# Digital_Input.net
KiCad netlist of a schematic drawn in Altium Designer
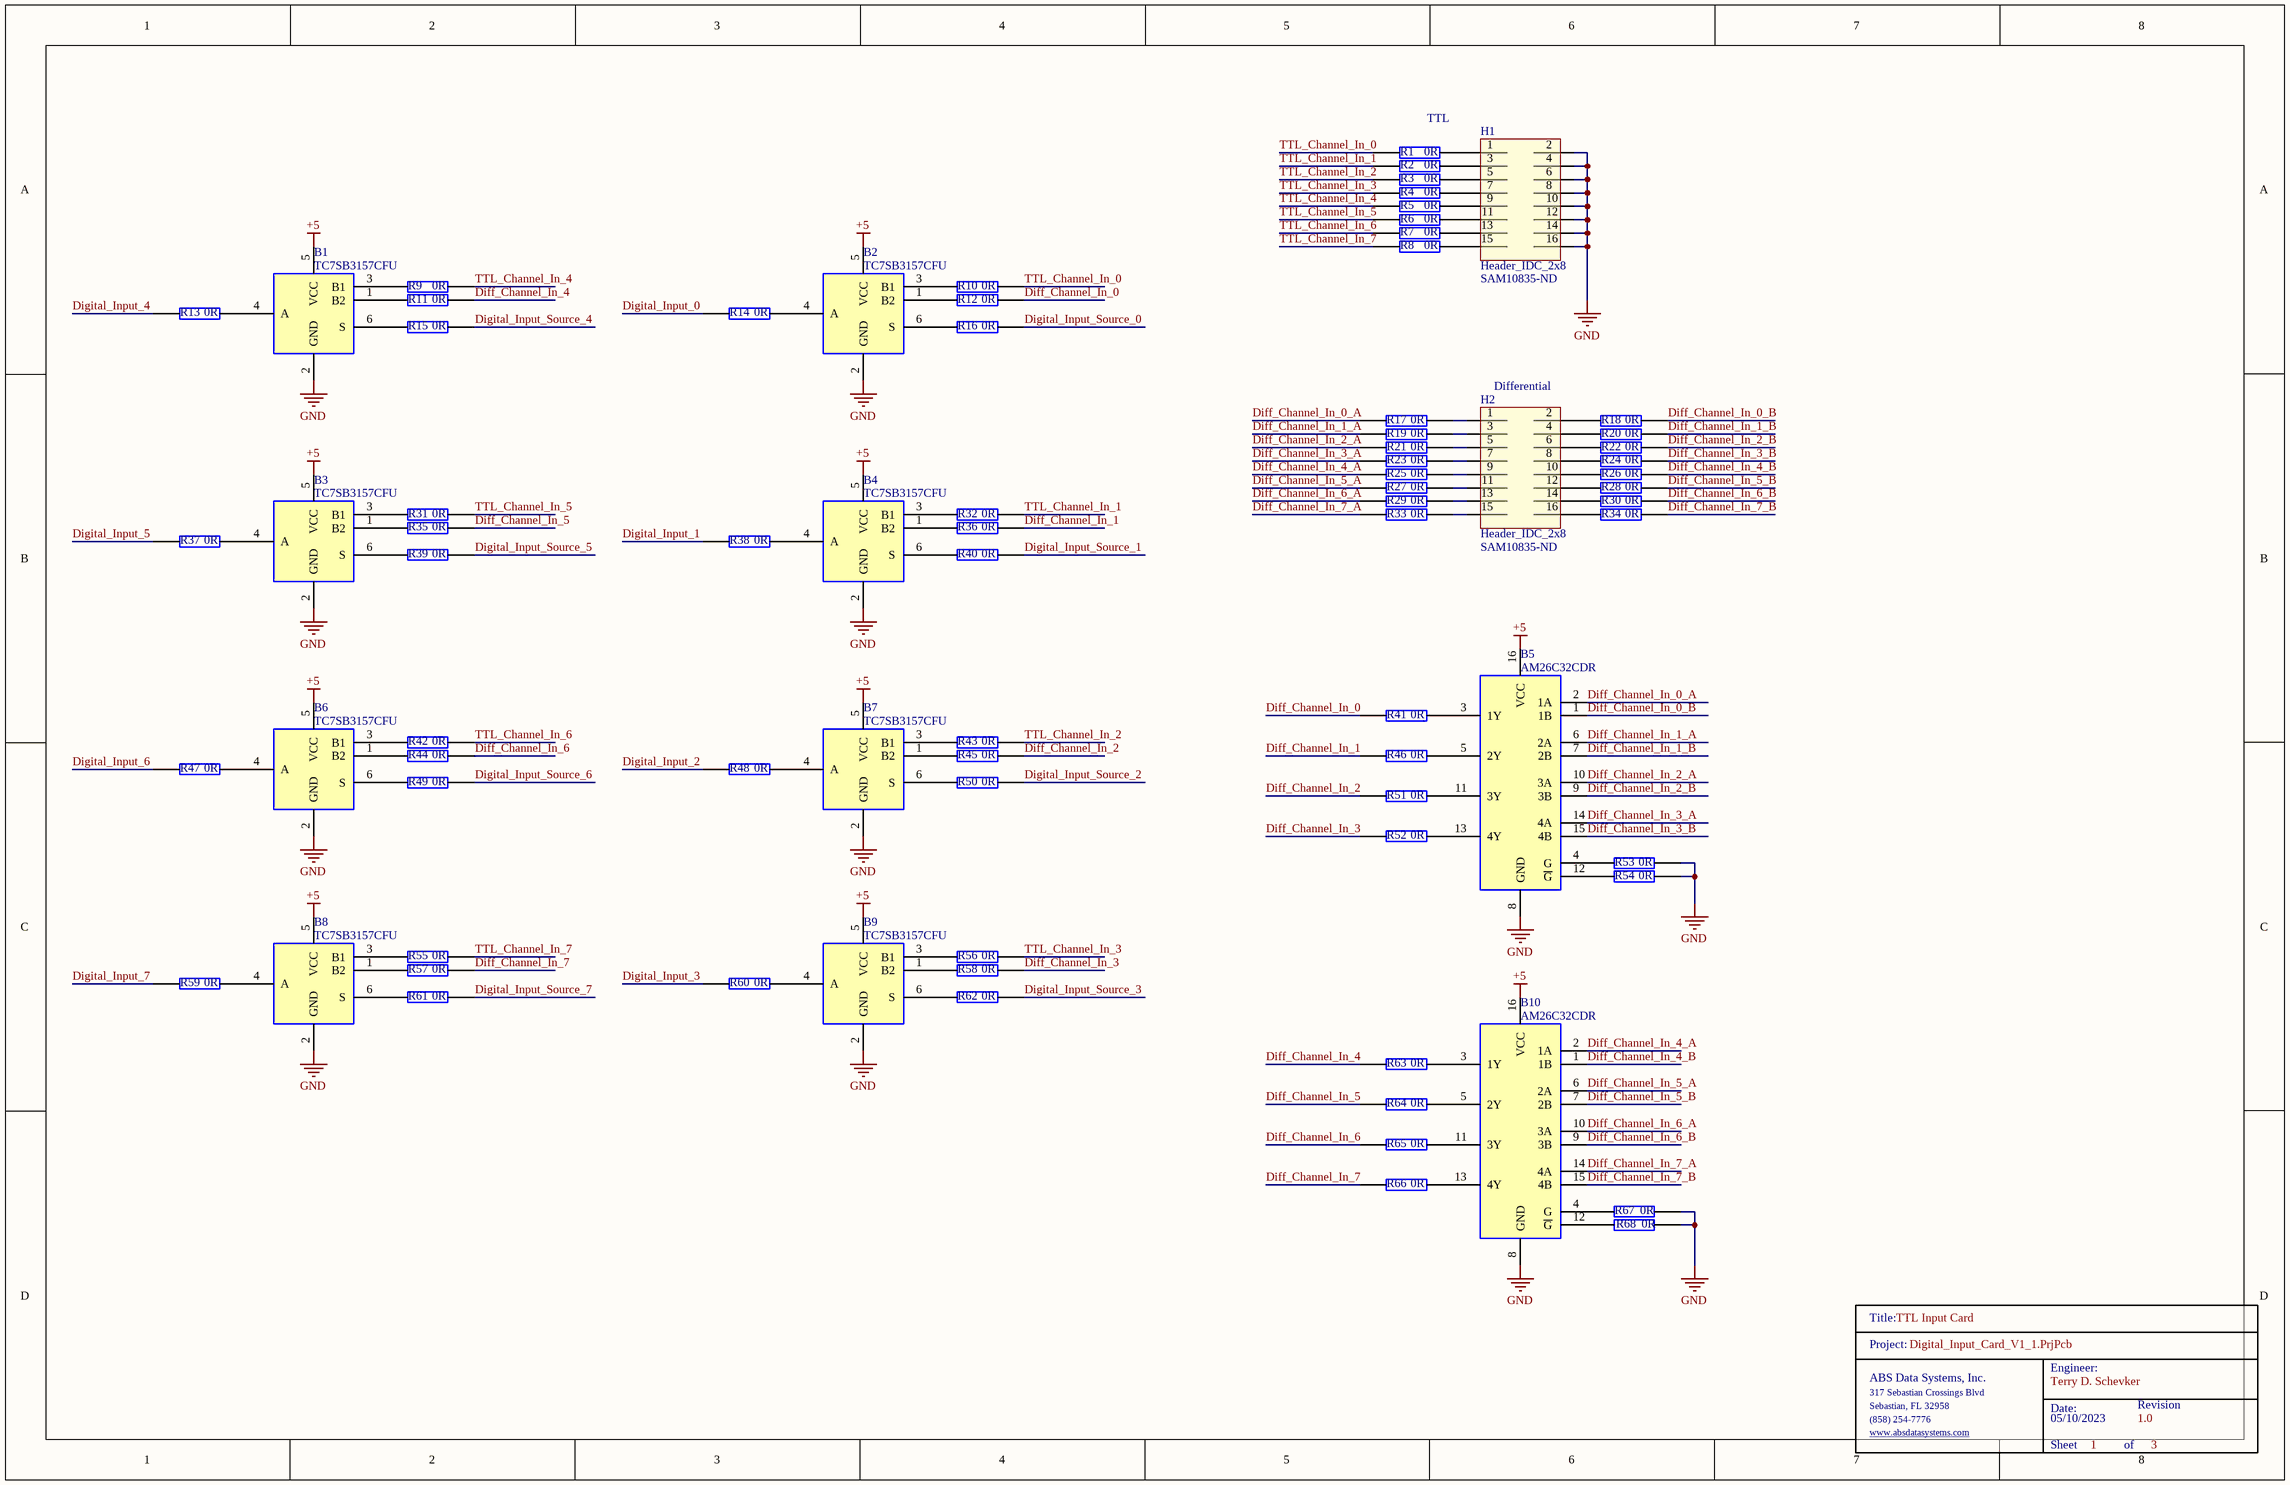
[diagram p0: Digital_Input.SchDoc]

(export (version "E")
  (design (tool "Eeschema 10.0.6"))
  (components
    (comp (ref "B1")
      (value "TC7SB3157CFU")
      (footprint "SOT-363-6")
      (description "TC7SB3157CFU MUX 2 in 1 out with control bit")
      (fields
        (field (name "MOUSER PART NUMBER") "771-PMP3906AYSH")
        (field (name "MANUFACTURER_PART_NUMBER") "PMP3906AYSH")
      )
      (libsource (lib "SemiConductors") (part "TC7SB3157CFU"))
    )
    (comp (ref "B2")
      (value "TC7SB3157CFU")
      (footprint "SOT-363-6")
      (description "TC7SB3157CFU MUX 2 in 1 out with control bit")
      (fields
        (field (name "MOUSER PART NUMBER") "771-PMP3906AYSH")
        (field (name "MANUFACTURER_PART_NUMBER") "PMP3906AYSH")
      )
      (libsource (lib "SemiConductors") (part "TC7SB3157CFU"))
    )
    (comp (ref "B3")
      (value "TC7SB3157CFU")
      (footprint "SOT-363-6")
      (description "TC7SB3157CFU MUX 2 in 1 out with control bit")
      (fields
        (field (name "MOUSER PART NUMBER") "771-PMP3906AYSH")
        (field (name "MANUFACTURER_PART_NUMBER") "PMP3906AYSH")
      )
      (libsource (lib "SemiConductors") (part "TC7SB3157CFU"))
    )
    (comp (ref "B4")
      (value "TC7SB3157CFU")
      (footprint "SOT-363-6")
      (description "TC7SB3157CFU MUX 2 in 1 out with control bit")
      (fields
        (field (name "MOUSER PART NUMBER") "771-PMP3906AYSH")
        (field (name "MANUFACTURER_PART_NUMBER") "PMP3906AYSH")
      )
      (libsource (lib "SemiConductors") (part "TC7SB3157CFU"))
    )
    (comp (ref "B5")
      (value "AM26C32CDR")
      (footprint "SOIC127P600X175-16N")
      (description "TEXAS INSTRUMENTS - AM26C32CDR - Receiver RS422/423, 4 Drivers, 4.5V-5.5V supply, SOIC-16")
      (fields (field (name "MOUSER PART NUMBER") "595-AM26C32CDR"))
      (libsource (lib "SemiConductors") (part "AM26C32CDR"))
    )
    (comp (ref "B6")
      (value "TC7SB3157CFU")
      (footprint "SOT-363-6")
      (description "TC7SB3157CFU MUX 2 in 1 out with control bit")
      (fields
        (field (name "MOUSER PART NUMBER") "771-PMP3906AYSH")
        (field (name "MANUFACTURER_PART_NUMBER") "PMP3906AYSH")
      )
      (libsource (lib "SemiConductors") (part "TC7SB3157CFU"))
    )
    (comp (ref "B7")
      (value "TC7SB3157CFU")
      (footprint "SOT-363-6")
      (description "TC7SB3157CFU MUX 2 in 1 out with control bit")
      (fields
        (field (name "MOUSER PART NUMBER") "771-PMP3906AYSH")
        (field (name "MANUFACTURER_PART_NUMBER") "PMP3906AYSH")
      )
      (libsource (lib "SemiConductors") (part "TC7SB3157CFU"))
    )
    (comp (ref "B8")
      (value "TC7SB3157CFU")
      (footprint "SOT-363-6")
      (description "TC7SB3157CFU MUX 2 in 1 out with control bit")
      (fields
        (field (name "MOUSER PART NUMBER") "771-PMP3906AYSH")
        (field (name "MANUFACTURER_PART_NUMBER") "PMP3906AYSH")
      )
      (libsource (lib "SemiConductors") (part "TC7SB3157CFU"))
    )
    (comp (ref "B9")
      (value "TC7SB3157CFU")
      (footprint "SOT-363-6")
      (description "TC7SB3157CFU MUX 2 in 1 out with control bit")
      (fields
        (field (name "MOUSER PART NUMBER") "771-PMP3906AYSH")
        (field (name "MANUFACTURER_PART_NUMBER") "PMP3906AYSH")
      )
      (libsource (lib "SemiConductors") (part "TC7SB3157CFU"))
    )
    (comp (ref "B10")
      (value "AM26C32CDR")
      (footprint "SOIC127P600X175-16N")
      (description "TEXAS INSTRUMENTS - AM26C32CDR - Receiver RS422/423, 4 Drivers, 4.5V-5.5V supply, SOIC-16")
      (fields (field (name "MOUSER PART NUMBER") "595-AM26C32CDR"))
      (libsource (lib "SemiConductors") (part "AM26C32CDR"))
    )
    (comp (ref "H1")
      (value "Header_IDC_2x8")
      (footprint "HDR2X8")
      (description "16 Pin 2x8 Through Hold IDC Connector")
      (fields
        (field (name "MANUFACTURER") "Samtec")
        (field (name "MANUFACTURER PART NUMBER") "TST-108-01-G-D")
        (field (name "SUPPLIER PART NUMBER 1") "SAM10835-ND")
      )
      (libsource (lib "Misc") (part "Header_IDC_2x8"))
    )
    (comp (ref "H2")
      (value "Header_IDC_2x8")
      (footprint "HDR2X8")
      (description "16 Pin 2x8 Through Hold IDC Connector")
      (fields
        (field (name "MANUFACTURER") "Samtec")
        (field (name "MANUFACTURER PART NUMBER") "TST-108-01-G-D")
        (field (name "SUPPLIER PART NUMBER 1") "SAM10835-ND")
      )
      (libsource (lib "Misc") (part "Header_IDC_2x8"))
    )
    (comp (ref "R1")
      (value "0R")
      (footprint "0603")
      (description "YAGEO 0603 0 ohm")
      (fields
        (field (name "MOUSER PART NUMBER") "603-RC0603JR-070RL")
        (field (name "MANUFACTURER_PART_NUMBER") "RC0603JR-070RL")
      )
      (libsource (lib "Resistors") (part "RC0603JR-070RL"))
    )
    (comp (ref "R2")
      (value "0R")
      (footprint "0603")
      (description "YAGEO 0603 0 ohm")
      (fields
        (field (name "MOUSER PART NUMBER") "603-RC0603JR-070RL")
        (field (name "MANUFACTURER_PART_NUMBER") "RC0603JR-070RL")
      )
      (libsource (lib "Resistors") (part "RC0603JR-070RL"))
    )
    (comp (ref "R3")
      (value "0R")
      (footprint "0603")
      (description "YAGEO 0603 0 ohm")
      (fields
        (field (name "MOUSER PART NUMBER") "603-RC0603JR-070RL")
        (field (name "MANUFACTURER_PART_NUMBER") "RC0603JR-070RL")
      )
      (libsource (lib "Resistors") (part "RC0603JR-070RL"))
    )
    (comp (ref "R4")
      (value "0R")
      (footprint "0603")
      (description "YAGEO 0603 0 ohm")
      (fields
        (field (name "MOUSER PART NUMBER") "603-RC0603JR-070RL")
        (field (name "MANUFACTURER_PART_NUMBER") "RC0603JR-070RL")
      )
      (libsource (lib "Resistors") (part "RC0603JR-070RL"))
    )
    (comp (ref "R5")
      (value "0R")
      (footprint "0603")
      (description "YAGEO 0603 0 ohm")
      (fields
        (field (name "MOUSER PART NUMBER") "603-RC0603JR-070RL")
        (field (name "MANUFACTURER_PART_NUMBER") "RC0603JR-070RL")
      )
      (libsource (lib "Resistors") (part "RC0603JR-070RL"))
    )
    (comp (ref "R6")
      (value "0R")
      (footprint "0603")
      (description "YAGEO 0603 0 ohm")
      (fields
        (field (name "MOUSER PART NUMBER") "603-RC0603JR-070RL")
        (field (name "MANUFACTURER_PART_NUMBER") "RC0603JR-070RL")
      )
      (libsource (lib "Resistors") (part "RC0603JR-070RL"))
    )
    (comp (ref "R7")
      (value "0R")
      (footprint "0603")
      (description "YAGEO 0603 0 ohm")
      (fields
        (field (name "MOUSER PART NUMBER") "603-RC0603JR-070RL")
        (field (name "MANUFACTURER_PART_NUMBER") "RC0603JR-070RL")
      )
      (libsource (lib "Resistors") (part "RC0603JR-070RL"))
    )
    (comp (ref "R8")
      (value "0R")
      (footprint "0603")
      (description "YAGEO 0603 0 ohm")
      (fields
        (field (name "MOUSER PART NUMBER") "603-RC0603JR-070RL")
        (field (name "MANUFACTURER_PART_NUMBER") "RC0603JR-070RL")
      )
      (libsource (lib "Resistors") (part "RC0603JR-070RL"))
    )
    (comp (ref "R9")
      (value "0R")
      (footprint "0603")
      (description "YAGEO 0603 0 ohm")
      (fields
        (field (name "MOUSER PART NUMBER") "603-RC0603JR-070RL")
        (field (name "MANUFACTURER_PART_NUMBER") "RC0603JR-070RL")
      )
      (libsource (lib "Resistors") (part "RC0603JR-070RL"))
    )
    (comp (ref "R10")
      (value "0R")
      (footprint "0603")
      (description "YAGEO 0603 0 ohm")
      (fields
        (field (name "MOUSER PART NUMBER") "603-RC0603JR-070RL")
        (field (name "MANUFACTURER_PART_NUMBER") "RC0603JR-070RL")
      )
      (libsource (lib "Resistors") (part "RC0603JR-070RL"))
    )
    (comp (ref "R11")
      (value "0R")
      (footprint "0603")
      (description "YAGEO 0603 0 ohm")
      (fields
        (field (name "MOUSER PART NUMBER") "603-RC0603JR-070RL")
        (field (name "MANUFACTURER_PART_NUMBER") "RC0603JR-070RL")
      )
      (libsource (lib "Resistors") (part "RC0603JR-070RL"))
    )
    (comp (ref "R12")
      (value "0R")
      (footprint "0603")
      (description "YAGEO 0603 0 ohm")
      (fields
        (field (name "MOUSER PART NUMBER") "603-RC0603JR-070RL")
        (field (name "MANUFACTURER_PART_NUMBER") "RC0603JR-070RL")
      )
      (libsource (lib "Resistors") (part "RC0603JR-070RL"))
    )
    (comp (ref "R13")
      (value "0R")
      (footprint "0603")
      (description "YAGEO 0603 0 ohm")
      (fields
        (field (name "MOUSER PART NUMBER") "603-RC0603JR-070RL")
        (field (name "MANUFACTURER_PART_NUMBER") "RC0603JR-070RL")
      )
      (libsource (lib "Resistors") (part "RC0603JR-070RL"))
    )
    (comp (ref "R14")
      (value "0R")
      (footprint "0603")
      (description "YAGEO 0603 0 ohm")
      (fields
        (field (name "MOUSER PART NUMBER") "603-RC0603JR-070RL")
        (field (name "MANUFACTURER_PART_NUMBER") "RC0603JR-070RL")
      )
      (libsource (lib "Resistors") (part "RC0603JR-070RL"))
    )
    (comp (ref "R15")
      (value "0R")
      (footprint "0603")
      (description "YAGEO 0603 0 ohm")
      (fields
        (field (name "MOUSER PART NUMBER") "603-RC0603JR-070RL")
        (field (name "MANUFACTURER_PART_NUMBER") "RC0603JR-070RL")
      )
      (libsource (lib "Resistors") (part "RC0603JR-070RL"))
    )
    (comp (ref "R16")
      (value "0R")
      (footprint "0603")
      (description "YAGEO 0603 0 ohm")
      (fields
        (field (name "MOUSER PART NUMBER") "603-RC0603JR-070RL")
        (field (name "MANUFACTURER_PART_NUMBER") "RC0603JR-070RL")
      )
      (libsource (lib "Resistors") (part "RC0603JR-070RL"))
    )
    (comp (ref "R17")
      (value "0R")
      (footprint "0603")
      (description "YAGEO 0603 0 ohm")
      (fields
        (field (name "MOUSER PART NUMBER") "603-RC0603JR-070RL")
        (field (name "MANUFACTURER_PART_NUMBER") "RC0603JR-070RL")
      )
      (libsource (lib "Resistors") (part "RC0603JR-070RL"))
    )
    (comp (ref "R18")
      (value "0R")
      (footprint "0603")
      (description "YAGEO 0603 0 ohm")
      (fields
        (field (name "MOUSER PART NUMBER") "603-RC0603JR-070RL")
        (field (name "MANUFACTURER_PART_NUMBER") "RC0603JR-070RL")
      )
      (libsource (lib "Resistors") (part "RC0603JR-070RL"))
    )
    (comp (ref "R19")
      (value "0R")
      (footprint "0603")
      (description "YAGEO 0603 0 ohm")
      (fields
        (field (name "MOUSER PART NUMBER") "603-RC0603JR-070RL")
        (field (name "MANUFACTURER_PART_NUMBER") "RC0603JR-070RL")
      )
      (libsource (lib "Resistors") (part "RC0603JR-070RL"))
    )
    (comp (ref "R20")
      (value "0R")
      (footprint "0603")
      (description "YAGEO 0603 0 ohm")
      (fields
        (field (name "MOUSER PART NUMBER") "603-RC0603JR-070RL")
        (field (name "MANUFACTURER_PART_NUMBER") "RC0603JR-070RL")
      )
      (libsource (lib "Resistors") (part "RC0603JR-070RL"))
    )
    (comp (ref "R21")
      (value "0R")
      (footprint "0603")
      (description "YAGEO 0603 0 ohm")
      (fields
        (field (name "MOUSER PART NUMBER") "603-RC0603JR-070RL")
        (field (name "MANUFACTURER_PART_NUMBER") "RC0603JR-070RL")
      )
      (libsource (lib "Resistors") (part "RC0603JR-070RL"))
    )
    (comp (ref "R22")
      (value "0R")
      (footprint "0603")
      (description "YAGEO 0603 0 ohm")
      (fields
        (field (name "MOUSER PART NUMBER") "603-RC0603JR-070RL")
        (field (name "MANUFACTURER_PART_NUMBER") "RC0603JR-070RL")
      )
      (libsource (lib "Resistors") (part "RC0603JR-070RL"))
    )
    (comp (ref "R23")
      (value "0R")
      (footprint "0603")
      (description "YAGEO 0603 0 ohm")
      (fields
        (field (name "MOUSER PART NUMBER") "603-RC0603JR-070RL")
        (field (name "MANUFACTURER_PART_NUMBER") "RC0603JR-070RL")
      )
      (libsource (lib "Resistors") (part "RC0603JR-070RL"))
    )
    (comp (ref "R24")
      (value "0R")
      (footprint "0603")
      (description "YAGEO 0603 0 ohm")
      (fields
        (field (name "MOUSER PART NUMBER") "603-RC0603JR-070RL")
        (field (name "MANUFACTURER_PART_NUMBER") "RC0603JR-070RL")
      )
      (libsource (lib "Resistors") (part "RC0603JR-070RL"))
    )
    (comp (ref "R25")
      (value "0R")
      (footprint "0603")
      (description "YAGEO 0603 0 ohm")
      (fields
        (field (name "MOUSER PART NUMBER") "603-RC0603JR-070RL")
        (field (name "MANUFACTURER_PART_NUMBER") "RC0603JR-070RL")
      )
      (libsource (lib "Resistors") (part "RC0603JR-070RL"))
    )
    (comp (ref "R26")
      (value "0R")
      (footprint "0603")
      (description "YAGEO 0603 0 ohm")
      (fields
        (field (name "MOUSER PART NUMBER") "603-RC0603JR-070RL")
        (field (name "MANUFACTURER_PART_NUMBER") "RC0603JR-070RL")
      )
      (libsource (lib "Resistors") (part "RC0603JR-070RL"))
    )
    (comp (ref "R27")
      (value "0R")
      (footprint "0603")
      (description "YAGEO 0603 0 ohm")
      (fields
        (field (name "MOUSER PART NUMBER") "603-RC0603JR-070RL")
        (field (name "MANUFACTURER_PART_NUMBER") "RC0603JR-070RL")
      )
      (libsource (lib "Resistors") (part "RC0603JR-070RL"))
    )
    (comp (ref "R28")
      (value "0R")
      (footprint "0603")
      (description "YAGEO 0603 0 ohm")
      (fields
        (field (name "MOUSER PART NUMBER") "603-RC0603JR-070RL")
        (field (name "MANUFACTURER_PART_NUMBER") "RC0603JR-070RL")
      )
      (libsource (lib "Resistors") (part "RC0603JR-070RL"))
    )
    (comp (ref "R29")
      (value "0R")
      (footprint "0603")
      (description "YAGEO 0603 0 ohm")
      (fields
        (field (name "MOUSER PART NUMBER") "603-RC0603JR-070RL")
        (field (name "MANUFACTURER_PART_NUMBER") "RC0603JR-070RL")
      )
      (libsource (lib "Resistors") (part "RC0603JR-070RL"))
    )
    (comp (ref "R30")
      (value "0R")
      (footprint "0603")
      (description "YAGEO 0603 0 ohm")
      (fields
        (field (name "MOUSER PART NUMBER") "603-RC0603JR-070RL")
        (field (name "MANUFACTURER_PART_NUMBER") "RC0603JR-070RL")
      )
      (libsource (lib "Resistors") (part "RC0603JR-070RL"))
    )
    (comp (ref "R31")
      (value "0R")
      (footprint "0603")
      (description "YAGEO 0603 0 ohm")
      (fields
        (field (name "MOUSER PART NUMBER") "603-RC0603JR-070RL")
        (field (name "MANUFACTURER_PART_NUMBER") "RC0603JR-070RL")
      )
      (libsource (lib "Resistors") (part "RC0603JR-070RL"))
    )
    (comp (ref "R32")
      (value "0R")
      (footprint "0603")
      (description "YAGEO 0603 0 ohm")
      (fields
        (field (name "MOUSER PART NUMBER") "603-RC0603JR-070RL")
        (field (name "MANUFACTURER_PART_NUMBER") "RC0603JR-070RL")
      )
      (libsource (lib "Resistors") (part "RC0603JR-070RL"))
    )
    (comp (ref "R33")
      (value "0R")
      (footprint "0603")
      (description "YAGEO 0603 0 ohm")
      (fields
        (field (name "MOUSER PART NUMBER") "603-RC0603JR-070RL")
        (field (name "MANUFACTURER_PART_NUMBER") "RC0603JR-070RL")
      )
      (libsource (lib "Resistors") (part "RC0603JR-070RL"))
    )
    (comp (ref "R34")
      (value "0R")
      (footprint "0603")
      (description "YAGEO 0603 0 ohm")
      (fields
        (field (name "MOUSER PART NUMBER") "603-RC0603JR-070RL")
        (field (name "MANUFACTURER_PART_NUMBER") "RC0603JR-070RL")
      )
      (libsource (lib "Resistors") (part "RC0603JR-070RL"))
    )
    (comp (ref "R35")
      (value "0R")
      (footprint "0603")
      (description "YAGEO 0603 0 ohm")
      (fields
        (field (name "MOUSER PART NUMBER") "603-RC0603JR-070RL")
        (field (name "MANUFACTURER_PART_NUMBER") "RC0603JR-070RL")
      )
      (libsource (lib "Resistors") (part "RC0603JR-070RL"))
    )
    (comp (ref "R36")
      (value "0R")
      (footprint "0603")
      (description "YAGEO 0603 0 ohm")
      (fields
        (field (name "MOUSER PART NUMBER") "603-RC0603JR-070RL")
        (field (name "MANUFACTURER_PART_NUMBER") "RC0603JR-070RL")
      )
      (libsource (lib "Resistors") (part "RC0603JR-070RL"))
    )
    (comp (ref "R37")
      (value "0R")
      (footprint "0603")
      (description "YAGEO 0603 0 ohm")
      (fields
        (field (name "MOUSER PART NUMBER") "603-RC0603JR-070RL")
        (field (name "MANUFACTURER_PART_NUMBER") "RC0603JR-070RL")
      )
      (libsource (lib "Resistors") (part "RC0603JR-070RL"))
    )
    (comp (ref "R38")
      (value "0R")
      (footprint "0603")
      (description "YAGEO 0603 0 ohm")
      (fields
        (field (name "MOUSER PART NUMBER") "603-RC0603JR-070RL")
        (field (name "MANUFACTURER_PART_NUMBER") "RC0603JR-070RL")
      )
      (libsource (lib "Resistors") (part "RC0603JR-070RL"))
    )
    (comp (ref "R39")
      (value "0R")
      (footprint "0603")
      (description "YAGEO 0603 0 ohm")
      (fields
        (field (name "MOUSER PART NUMBER") "603-RC0603JR-070RL")
        (field (name "MANUFACTURER_PART_NUMBER") "RC0603JR-070RL")
      )
      (libsource (lib "Resistors") (part "RC0603JR-070RL"))
    )
    (comp (ref "R40")
      (value "0R")
      (footprint "0603")
      (description "YAGEO 0603 0 ohm")
      (fields
        (field (name "MOUSER PART NUMBER") "603-RC0603JR-070RL")
        (field (name "MANUFACTURER_PART_NUMBER") "RC0603JR-070RL")
      )
      (libsource (lib "Resistors") (part "RC0603JR-070RL"))
    )
    (comp (ref "R41")
      (value "0R")
      (footprint "0603")
      (description "YAGEO 0603 0 ohm")
      (fields
        (field (name "MOUSER PART NUMBER") "603-RC0603JR-070RL")
        (field (name "MANUFACTURER_PART_NUMBER") "RC0603JR-070RL")
      )
      (libsource (lib "Resistors") (part "RC0603JR-070RL"))
    )
    (comp (ref "R42")
      (value "0R")
      (footprint "0603")
      (description "YAGEO 0603 0 ohm")
      (fields
        (field (name "MOUSER PART NUMBER") "603-RC0603JR-070RL")
        (field (name "MANUFACTURER_PART_NUMBER") "RC0603JR-070RL")
      )
      (libsource (lib "Resistors") (part "RC0603JR-070RL"))
    )
    (comp (ref "R43")
      (value "0R")
      (footprint "0603")
      (description "YAGEO 0603 0 ohm")
      (fields
        (field (name "MOUSER PART NUMBER") "603-RC0603JR-070RL")
        (field (name "MANUFACTURER_PART_NUMBER") "RC0603JR-070RL")
      )
      (libsource (lib "Resistors") (part "RC0603JR-070RL"))
    )
    (comp (ref "R44")
      (value "0R")
      (footprint "0603")
      (description "YAGEO 0603 0 ohm")
      (fields
        (field (name "MOUSER PART NUMBER") "603-RC0603JR-070RL")
        (field (name "MANUFACTURER_PART_NUMBER") "RC0603JR-070RL")
      )
      (libsource (lib "Resistors") (part "RC0603JR-070RL"))
    )
    (comp (ref "R45")
      (value "0R")
      (footprint "0603")
      (description "YAGEO 0603 0 ohm")
      (fields
        (field (name "MOUSER PART NUMBER") "603-RC0603JR-070RL")
        (field (name "MANUFACTURER_PART_NUMBER") "RC0603JR-070RL")
      )
      (libsource (lib "Resistors") (part "RC0603JR-070RL"))
    )
    (comp (ref "R46")
      (value "0R")
      (footprint "0603")
      (description "YAGEO 0603 0 ohm")
      (fields
        (field (name "MOUSER PART NUMBER") "603-RC0603JR-070RL")
        (field (name "MANUFACTURER_PART_NUMBER") "RC0603JR-070RL")
      )
      (libsource (lib "Resistors") (part "RC0603JR-070RL"))
    )
    (comp (ref "R47")
      (value "0R")
      (footprint "0603")
      (description "YAGEO 0603 0 ohm")
      (fields
        (field (name "MOUSER PART NUMBER") "603-RC0603JR-070RL")
        (field (name "MANUFACTURER_PART_NUMBER") "RC0603JR-070RL")
      )
      (libsource (lib "Resistors") (part "RC0603JR-070RL"))
    )
    (comp (ref "R48")
      (value "0R")
      (footprint "0603")
      (description "YAGEO 0603 0 ohm")
      (fields
        (field (name "MOUSER PART NUMBER") "603-RC0603JR-070RL")
        (field (name "MANUFACTURER_PART_NUMBER") "RC0603JR-070RL")
      )
      (libsource (lib "Resistors") (part "RC0603JR-070RL"))
    )
    (comp (ref "R49")
      (value "0R")
      (footprint "0603")
      (description "YAGEO 0603 0 ohm")
      (fields
        (field (name "MOUSER PART NUMBER") "603-RC0603JR-070RL")
        (field (name "MANUFACTURER_PART_NUMBER") "RC0603JR-070RL")
      )
      (libsource (lib "Resistors") (part "RC0603JR-070RL"))
    )
    (comp (ref "R50")
      (value "0R")
      (footprint "0603")
      (description "YAGEO 0603 0 ohm")
      (fields
        (field (name "MOUSER PART NUMBER") "603-RC0603JR-070RL")
        (field (name "MANUFACTURER_PART_NUMBER") "RC0603JR-070RL")
      )
      (libsource (lib "Resistors") (part "RC0603JR-070RL"))
    )
    (comp (ref "R51")
      (value "0R")
      (footprint "0603")
      (description "YAGEO 0603 0 ohm")
      (fields
        (field (name "MOUSER PART NUMBER") "603-RC0603JR-070RL")
        (field (name "MANUFACTURER_PART_NUMBER") "RC0603JR-070RL")
      )
      (libsource (lib "Resistors") (part "RC0603JR-070RL"))
    )
    (comp (ref "R52")
      (value "0R")
      (footprint "0603")
      (description "YAGEO 0603 0 ohm")
      (fields
        (field (name "MOUSER PART NUMBER") "603-RC0603JR-070RL")
        (field (name "MANUFACTURER_PART_NUMBER") "RC0603JR-070RL")
      )
      (libsource (lib "Resistors") (part "RC0603JR-070RL"))
    )
    (comp (ref "R53")
      (value "0R")
      (footprint "0603")
      (description "YAGEO 0603 0 ohm")
      (fields
        (field (name "MOUSER PART NUMBER") "603-RC0603JR-070RL")
        (field (name "MANUFACTURER_PART_NUMBER") "RC0603JR-070RL")
      )
      (libsource (lib "Resistors") (part "RC0603JR-070RL"))
    )
    (comp (ref "R54")
      (value "0R")
      (footprint "0603")
      (description "YAGEO 0603 0 ohm")
      (fields
        (field (name "MOUSER PART NUMBER") "603-RC0603JR-070RL")
        (field (name "MANUFACTURER_PART_NUMBER") "RC0603JR-070RL")
      )
      (libsource (lib "Resistors") (part "RC0603JR-070RL"))
    )
    (comp (ref "R55")
      (value "0R")
      (footprint "0603")
      (description "YAGEO 0603 0 ohm")
      (fields
        (field (name "MOUSER PART NUMBER") "603-RC0603JR-070RL")
        (field (name "MANUFACTURER_PART_NUMBER") "RC0603JR-070RL")
      )
      (libsource (lib "Resistors") (part "RC0603JR-070RL"))
    )
    (comp (ref "R56")
      (value "0R")
      (footprint "0603")
      (description "YAGEO 0603 0 ohm")
      (fields
        (field (name "MOUSER PART NUMBER") "603-RC0603JR-070RL")
        (field (name "MANUFACTURER_PART_NUMBER") "RC0603JR-070RL")
      )
      (libsource (lib "Resistors") (part "RC0603JR-070RL"))
    )
    (comp (ref "R57")
      (value "0R")
      (footprint "0603")
      (description "YAGEO 0603 0 ohm")
      (fields
        (field (name "MOUSER PART NUMBER") "603-RC0603JR-070RL")
        (field (name "MANUFACTURER_PART_NUMBER") "RC0603JR-070RL")
      )
      (libsource (lib "Resistors") (part "RC0603JR-070RL"))
    )
    (comp (ref "R58")
      (value "0R")
      (footprint "0603")
      (description "YAGEO 0603 0 ohm")
      (fields
        (field (name "MOUSER PART NUMBER") "603-RC0603JR-070RL")
        (field (name "MANUFACTURER_PART_NUMBER") "RC0603JR-070RL")
      )
      (libsource (lib "Resistors") (part "RC0603JR-070RL"))
    )
    (comp (ref "R59")
      (value "0R")
      (footprint "0603")
      (description "YAGEO 0603 0 ohm")
      (fields
        (field (name "MOUSER PART NUMBER") "603-RC0603JR-070RL")
        (field (name "MANUFACTURER_PART_NUMBER") "RC0603JR-070RL")
      )
      (libsource (lib "Resistors") (part "RC0603JR-070RL"))
    )
    (comp (ref "R60")
      (value "0R")
      (footprint "0603")
      (description "YAGEO 0603 0 ohm")
      (fields
        (field (name "MOUSER PART NUMBER") "603-RC0603JR-070RL")
        (field (name "MANUFACTURER_PART_NUMBER") "RC0603JR-070RL")
      )
      (libsource (lib "Resistors") (part "RC0603JR-070RL"))
    )
    (comp (ref "R61")
      (value "0R")
      (footprint "0603")
      (description "YAGEO 0603 0 ohm")
      (fields
        (field (name "MOUSER PART NUMBER") "603-RC0603JR-070RL")
        (field (name "MANUFACTURER_PART_NUMBER") "RC0603JR-070RL")
      )
      (libsource (lib "Resistors") (part "RC0603JR-070RL"))
    )
    (comp (ref "R62")
      (value "0R")
      (footprint "0603")
      (description "YAGEO 0603 0 ohm")
      (fields
        (field (name "MOUSER PART NUMBER") "603-RC0603JR-070RL")
        (field (name "MANUFACTURER_PART_NUMBER") "RC0603JR-070RL")
      )
      (libsource (lib "Resistors") (part "RC0603JR-070RL"))
    )
    (comp (ref "R63")
      (value "0R")
      (footprint "0603")
      (description "YAGEO 0603 0 ohm")
      (fields
        (field (name "MOUSER PART NUMBER") "603-RC0603JR-070RL")
        (field (name "MANUFACTURER_PART_NUMBER") "RC0603JR-070RL")
      )
      (libsource (lib "Resistors") (part "RC0603JR-070RL"))
    )
    (comp (ref "R64")
      (value "0R")
      (footprint "0603")
      (description "YAGEO 0603 0 ohm")
      (fields
        (field (name "MOUSER PART NUMBER") "603-RC0603JR-070RL")
        (field (name "MANUFACTURER_PART_NUMBER") "RC0603JR-070RL")
      )
      (libsource (lib "Resistors") (part "RC0603JR-070RL"))
    )
    (comp (ref "R65")
      (value "0R")
      (footprint "0603")
      (description "YAGEO 0603 0 ohm")
      (fields
        (field (name "MOUSER PART NUMBER") "603-RC0603JR-070RL")
        (field (name "MANUFACTURER_PART_NUMBER") "RC0603JR-070RL")
      )
      (libsource (lib "Resistors") (part "RC0603JR-070RL"))
    )
    (comp (ref "R66")
      (value "0R")
      (footprint "0603")
      (description "YAGEO 0603 0 ohm")
      (fields
        (field (name "MOUSER PART NUMBER") "603-RC0603JR-070RL")
        (field (name "MANUFACTURER_PART_NUMBER") "RC0603JR-070RL")
      )
      (libsource (lib "Resistors") (part "RC0603JR-070RL"))
    )
    (comp (ref "R67")
      (value "0R")
      (footprint "0603")
      (description "YAGEO 0603 0 ohm")
      (fields
        (field (name "MOUSER PART NUMBER") "603-RC0603JR-070RL")
        (field (name "MANUFACTURER_PART_NUMBER") "RC0603JR-070RL")
      )
      (libsource (lib "Resistors") (part "RC0603JR-070RL"))
    )
    (comp (ref "R68")
      (value "0R")
      (footprint "0603")
      (description "YAGEO 0603 0 ohm")
      (fields
        (field (name "MOUSER PART NUMBER") "603-RC0603JR-070RL")
        (field (name "MANUFACTURER_PART_NUMBER") "RC0603JR-070RL")
      )
      (libsource (lib "Resistors") (part "RC0603JR-070RL"))
    )
    (comp (ref "TitleBlock_4") (value "TitleBlock") (libsource (lib "Misc") (part "TitleBlock")))
  )
  (nets
    (net (code "1") (name "+5") (class "Default")
      (node (ref "B1") (pin "5") (pinfunction "VCC_5") (pintype "passive"))
      (node (ref "B10") (pin "16") (pinfunction "VCC_16") (pintype "power_in"))
      (node (ref "B2") (pin "5") (pinfunction "VCC_5") (pintype "passive"))
      (node (ref "B3") (pin "5") (pinfunction "VCC_5") (pintype "passive"))
      (node (ref "B4") (pin "5") (pinfunction "VCC_5") (pintype "passive"))
      (node (ref "B5") (pin "16") (pinfunction "VCC_16") (pintype "power_in"))
      (node (ref "B6") (pin "5") (pinfunction "VCC_5") (pintype "passive"))
      (node (ref "B7") (pin "5") (pinfunction "VCC_5") (pintype "passive"))
      (node (ref "B8") (pin "5") (pinfunction "VCC_5") (pintype "passive"))
      (node (ref "B9") (pin "5") (pinfunction "VCC_5") (pintype "passive"))
    )
    (net (code "2") (name "/Diff_Channel_In_0") (class "Default")
      (node (ref "R12") (pin "2") (pinfunction "2_2") (pintype "passive"))
      (node (ref "R41") (pin "1") (pinfunction "1_1") (pintype "passive"))
    )
    (net (code "3") (name "/Diff_Channel_In_0_A") (class "Default")
      (node (ref "B5") (pin "2") (pinfunction "1A_2") (pintype "passive"))
      (node (ref "R17") (pin "1") (pinfunction "1_1") (pintype "passive"))
    )
    (net (code "4") (name "/Diff_Channel_In_0_B") (class "Default")
      (node (ref "B5") (pin "1") (pinfunction "1B_1") (pintype "passive"))
      (node (ref "R18") (pin "2") (pinfunction "2_2") (pintype "passive"))
    )
    (net (code "5") (name "/Diff_Channel_In_1") (class "Default")
      (node (ref "R36") (pin "2") (pinfunction "2_2") (pintype "passive"))
      (node (ref "R46") (pin "1") (pinfunction "1_1") (pintype "passive"))
    )
    (net (code "6") (name "/Diff_Channel_In_1_A") (class "Default")
      (node (ref "B5") (pin "6") (pinfunction "2A_6") (pintype "passive"))
      (node (ref "R19") (pin "1") (pinfunction "1_1") (pintype "passive"))
    )
    (net (code "7") (name "/Diff_Channel_In_1_B") (class "Default")
      (node (ref "B5") (pin "7") (pinfunction "2B_7") (pintype "passive"))
      (node (ref "R20") (pin "2") (pinfunction "2_2") (pintype "passive"))
    )
    (net (code "8") (name "/Diff_Channel_In_2") (class "Default")
      (node (ref "R45") (pin "2") (pinfunction "2_2") (pintype "passive"))
      (node (ref "R51") (pin "1") (pinfunction "1_1") (pintype "passive"))
    )
    (net (code "9") (name "/Diff_Channel_In_2_A") (class "Default")
      (node (ref "B5") (pin "10") (pinfunction "3A_10") (pintype "passive"))
      (node (ref "R21") (pin "1") (pinfunction "1_1") (pintype "passive"))
    )
    (net (code "10") (name "/Diff_Channel_In_2_B") (class "Default")
      (node (ref "B5") (pin "9") (pinfunction "3B_9") (pintype "passive"))
      (node (ref "R22") (pin "2") (pinfunction "2_2") (pintype "passive"))
    )
    (net (code "11") (name "/Diff_Channel_In_3") (class "Default")
      (node (ref "R52") (pin "1") (pinfunction "1_1") (pintype "passive"))
      (node (ref "R58") (pin "2") (pinfunction "2_2") (pintype "passive"))
    )
    (net (code "12") (name "/Diff_Channel_In_3_A") (class "Default")
      (node (ref "B5") (pin "14") (pinfunction "4A_14") (pintype "passive"))
      (node (ref "R23") (pin "1") (pinfunction "1_1") (pintype "passive"))
    )
    (net (code "13") (name "/Diff_Channel_In_3_B") (class "Default")
      (node (ref "B5") (pin "15") (pinfunction "4B_15") (pintype "passive"))
      (node (ref "R24") (pin "2") (pinfunction "2_2") (pintype "passive"))
    )
    (net (code "14") (name "/Diff_Channel_In_4") (class "Default")
      (node (ref "R11") (pin "2") (pinfunction "2_2") (pintype "passive"))
      (node (ref "R63") (pin "1") (pinfunction "1_1") (pintype "passive"))
    )
    (net (code "15") (name "/Diff_Channel_In_4_A") (class "Default")
      (node (ref "B10") (pin "2") (pinfunction "1A_2") (pintype "passive"))
      (node (ref "R25") (pin "1") (pinfunction "1_1") (pintype "passive"))
    )
    (net (code "16") (name "/Diff_Channel_In_4_B") (class "Default")
      (node (ref "B10") (pin "1") (pinfunction "1B_1") (pintype "passive"))
      (node (ref "R26") (pin "2") (pinfunction "2_2") (pintype "passive"))
    )
    (net (code "17") (name "/Diff_Channel_In_5") (class "Default")
      (node (ref "R35") (pin "2") (pinfunction "2_2") (pintype "passive"))
      (node (ref "R64") (pin "1") (pinfunction "1_1") (pintype "passive"))
    )
    (net (code "18") (name "/Diff_Channel_In_5_A") (class "Default")
      (node (ref "B10") (pin "6") (pinfunction "2A_6") (pintype "passive"))
      (node (ref "R27") (pin "1") (pinfunction "1_1") (pintype "passive"))
    )
    (net (code "19") (name "/Diff_Channel_In_5_B") (class "Default")
      (node (ref "B10") (pin "7") (pinfunction "2B_7") (pintype "passive"))
      (node (ref "R28") (pin "2") (pinfunction "2_2") (pintype "passive"))
    )
    (net (code "20") (name "/Diff_Channel_In_6") (class "Default")
      (node (ref "R44") (pin "2") (pinfunction "2_2") (pintype "passive"))
      (node (ref "R65") (pin "1") (pinfunction "1_1") (pintype "passive"))
    )
    (net (code "21") (name "/Diff_Channel_In_6_A") (class "Default")
      (node (ref "B10") (pin "10") (pinfunction "3A_10") (pintype "passive"))
      (node (ref "R29") (pin "1") (pinfunction "1_1") (pintype "passive"))
    )
    (net (code "22") (name "/Diff_Channel_In_6_B") (class "Default")
      (node (ref "B10") (pin "9") (pinfunction "3B_9") (pintype "passive"))
      (node (ref "R30") (pin "2") (pinfunction "2_2") (pintype "passive"))
    )
    (net (code "23") (name "/Diff_Channel_In_7") (class "Default")
      (node (ref "R57") (pin "2") (pinfunction "2_2") (pintype "passive"))
      (node (ref "R66") (pin "1") (pinfunction "1_1") (pintype "passive"))
    )
    (net (code "24") (name "/Diff_Channel_In_7_A") (class "Default")
      (node (ref "B10") (pin "14") (pinfunction "4A_14") (pintype "passive"))
      (node (ref "R33") (pin "1") (pinfunction "1_1") (pintype "passive"))
    )
    (net (code "25") (name "/Diff_Channel_In_7_B") (class "Default")
      (node (ref "B10") (pin "15") (pinfunction "4B_15") (pintype "passive"))
      (node (ref "R34") (pin "2") (pinfunction "2_2") (pintype "passive"))
    )
    (net (code "26") (name "/Digital_Input_0") (class "Default")
      (node (ref "R14") (pin "1") (pinfunction "1_1") (pintype "passive"))
    )
    (net (code "27") (name "/Digital_Input_1") (class "Default")
      (node (ref "R38") (pin "1") (pinfunction "1_1") (pintype "passive"))
    )
    (net (code "28") (name "/Digital_Input_2") (class "Default")
      (node (ref "R48") (pin "1") (pinfunction "1_1") (pintype "passive"))
    )
    (net (code "29") (name "/Digital_Input_3") (class "Default")
      (node (ref "R60") (pin "1") (pinfunction "1_1") (pintype "passive"))
    )
    (net (code "30") (name "/Digital_Input_4") (class "Default")
      (node (ref "R13") (pin "1") (pinfunction "1_1") (pintype "passive"))
    )
    (net (code "31") (name "/Digital_Input_5") (class "Default")
      (node (ref "R37") (pin "1") (pinfunction "1_1") (pintype "passive"))
    )
    (net (code "32") (name "/Digital_Input_6") (class "Default")
      (node (ref "R47") (pin "1") (pinfunction "1_1") (pintype "passive"))
    )
    (net (code "33") (name "/Digital_Input_7") (class "Default")
      (node (ref "R59") (pin "1") (pinfunction "1_1") (pintype "passive"))
    )
    (net (code "34") (name "/Digital_Input_Source_0") (class "Default")
      (node (ref "R16") (pin "2") (pinfunction "2_2") (pintype "passive"))
    )
    (net (code "35") (name "/Digital_Input_Source_1") (class "Default")
      (node (ref "R40") (pin "2") (pinfunction "2_2") (pintype "passive"))
    )
    (net (code "36") (name "/Digital_Input_Source_2") (class "Default")
      (node (ref "R50") (pin "2") (pinfunction "2_2") (pintype "passive"))
    )
    (net (code "37") (name "/Digital_Input_Source_3") (class "Default")
      (node (ref "R62") (pin "2") (pinfunction "2_2") (pintype "passive"))
    )
    (net (code "38") (name "/Digital_Input_Source_4") (class "Default")
      (node (ref "R15") (pin "2") (pinfunction "2_2") (pintype "passive"))
    )
    (net (code "39") (name "/Digital_Input_Source_5") (class "Default")
      (node (ref "R39") (pin "2") (pinfunction "2_2") (pintype "passive"))
    )
    (net (code "40") (name "/Digital_Input_Source_6") (class "Default")
      (node (ref "R49") (pin "2") (pinfunction "2_2") (pintype "passive"))
    )
    (net (code "41") (name "/Digital_Input_Source_7") (class "Default")
      (node (ref "R61") (pin "2") (pinfunction "2_2") (pintype "passive"))
    )
    (net (code "42") (name "/TTL_Channel_In_0") (class "Default")
      (node (ref "R1") (pin "1") (pinfunction "1_1") (pintype "passive"))
      (node (ref "R10") (pin "2") (pinfunction "2_2") (pintype "passive"))
    )
    (net (code "43") (name "/TTL_Channel_In_1") (class "Default")
      (node (ref "R2") (pin "1") (pinfunction "1_1") (pintype "passive"))
      (node (ref "R32") (pin "2") (pinfunction "2_2") (pintype "passive"))
    )
    (net (code "44") (name "/TTL_Channel_In_2") (class "Default")
      (node (ref "R3") (pin "1") (pinfunction "1_1") (pintype "passive"))
      (node (ref "R43") (pin "2") (pinfunction "2_2") (pintype "passive"))
    )
    (net (code "45") (name "/TTL_Channel_In_3") (class "Default")
      (node (ref "R4") (pin "1") (pinfunction "1_1") (pintype "passive"))
      (node (ref "R56") (pin "2") (pinfunction "2_2") (pintype "passive"))
    )
    (net (code "46") (name "/TTL_Channel_In_4") (class "Default")
      (node (ref "R5") (pin "1") (pinfunction "1_1") (pintype "passive"))
      (node (ref "R9") (pin "2") (pinfunction "2_2") (pintype "passive"))
    )
    (net (code "47") (name "/TTL_Channel_In_5") (class "Default")
      (node (ref "R31") (pin "2") (pinfunction "2_2") (pintype "passive"))
      (node (ref "R6") (pin "1") (pinfunction "1_1") (pintype "passive"))
    )
    (net (code "48") (name "/TTL_Channel_In_6") (class "Default")
      (node (ref "R42") (pin "2") (pinfunction "2_2") (pintype "passive"))
      (node (ref "R7") (pin "1") (pinfunction "1_1") (pintype "passive"))
    )
    (net (code "49") (name "/TTL_Channel_In_7") (class "Default")
      (node (ref "R55") (pin "2") (pinfunction "2_2") (pintype "passive"))
      (node (ref "R8") (pin "1") (pinfunction "1_1") (pintype "passive"))
    )
    (net (code "50") (name "GND") (class "Default")
      (node (ref "B1") (pin "2") (pinfunction "GND_2") (pintype "passive"))
      (node (ref "B10") (pin "8") (pinfunction "GND_8") (pintype "passive"))
      (node (ref "B2") (pin "2") (pinfunction "GND_2") (pintype "passive"))
      (node (ref "B3") (pin "2") (pinfunction "GND_2") (pintype "passive"))
      (node (ref "B4") (pin "2") (pinfunction "GND_2") (pintype "passive"))
      (node (ref "B5") (pin "8") (pinfunction "GND_8") (pintype "passive"))
      (node (ref "B6") (pin "2") (pinfunction "GND_2") (pintype "passive"))
      (node (ref "B7") (pin "2") (pinfunction "GND_2") (pintype "passive"))
      (node (ref "B8") (pin "2") (pinfunction "GND_2") (pintype "passive"))
      (node (ref "B9") (pin "2") (pinfunction "GND_2") (pintype "passive"))
      (node (ref "H1") (pin "10") (pinfunction "10_10") (pintype "passive"))
      (node (ref "H1") (pin "12") (pinfunction "12_12") (pintype "passive"))
      (node (ref "H1") (pin "14") (pinfunction "14_14") (pintype "passive"))
      (node (ref "H1") (pin "16") (pinfunction "16_16") (pintype "passive"))
      (node (ref "H1") (pin "2") (pinfunction "2_2") (pintype "passive"))
      (node (ref "H1") (pin "4") (pinfunction "4_4") (pintype "passive"))
      (node (ref "H1") (pin "6") (pinfunction "6_6") (pintype "passive"))
      (node (ref "H1") (pin "8") (pinfunction "8_8") (pintype "passive"))
      (node (ref "R53") (pin "2") (pinfunction "2_2") (pintype "passive"))
      (node (ref "R54") (pin "2") (pinfunction "2_2") (pintype "passive"))
      (node (ref "R67") (pin "2") (pinfunction "2_2") (pintype "passive"))
      (node (ref "R68") (pin "2") (pinfunction "2_2") (pintype "passive"))
    )
    (net (code "51") (name "Net-(B1-A)") (class "Default")
      (node (ref "B1") (pin "4") (pinfunction "A_4") (pintype "passive"))
      (node (ref "R13") (pin "2") (pinfunction "2_2") (pintype "passive"))
    )
    (net (code "52") (name "Net-(B1-B1)") (class "Default")
      (node (ref "B1") (pin "3") (pinfunction "B1_3") (pintype "passive"))
      (node (ref "R9") (pin "1") (pinfunction "1_1") (pintype "passive"))
    )
    (net (code "53") (name "Net-(B1-B2)") (class "Default")
      (node (ref "B1") (pin "1") (pinfunction "B2_1") (pintype "passive"))
      (node (ref "R11") (pin "1") (pinfunction "1_1") (pintype "passive"))
    )
    (net (code "54") (name "Net-(B1-S)") (class "Default")
      (node (ref "B1") (pin "6") (pinfunction "S_6") (pintype "passive"))
      (node (ref "R15") (pin "1") (pinfunction "1_1") (pintype "passive"))
    )
    (net (code "55") (name "Net-(B2-A)") (class "Default")
      (node (ref "B2") (pin "4") (pinfunction "A_4") (pintype "passive"))
      (node (ref "R14") (pin "2") (pinfunction "2_2") (pintype "passive"))
    )
    (net (code "56") (name "Net-(B2-B1)") (class "Default")
      (node (ref "B2") (pin "3") (pinfunction "B1_3") (pintype "passive"))
      (node (ref "R10") (pin "1") (pinfunction "1_1") (pintype "passive"))
    )
    (net (code "57") (name "Net-(B2-B2)") (class "Default")
      (node (ref "B2") (pin "1") (pinfunction "B2_1") (pintype "passive"))
      (node (ref "R12") (pin "1") (pinfunction "1_1") (pintype "passive"))
    )
    (net (code "58") (name "Net-(B2-S)") (class "Default")
      (node (ref "B2") (pin "6") (pinfunction "S_6") (pintype "passive"))
      (node (ref "R16") (pin "1") (pinfunction "1_1") (pintype "passive"))
    )
    (net (code "59") (name "Net-(B3-A)") (class "Default")
      (node (ref "B3") (pin "4") (pinfunction "A_4") (pintype "passive"))
      (node (ref "R37") (pin "2") (pinfunction "2_2") (pintype "passive"))
    )
    (net (code "60") (name "Net-(B3-B1)") (class "Default")
      (node (ref "B3") (pin "3") (pinfunction "B1_3") (pintype "passive"))
      (node (ref "R31") (pin "1") (pinfunction "1_1") (pintype "passive"))
    )
    (net (code "61") (name "Net-(B3-B2)") (class "Default")
      (node (ref "B3") (pin "1") (pinfunction "B2_1") (pintype "passive"))
      (node (ref "R35") (pin "1") (pinfunction "1_1") (pintype "passive"))
    )
    (net (code "62") (name "Net-(B3-S)") (class "Default")
      (node (ref "B3") (pin "6") (pinfunction "S_6") (pintype "passive"))
      (node (ref "R39") (pin "1") (pinfunction "1_1") (pintype "passive"))
    )
    (net (code "63") (name "Net-(B4-A)") (class "Default")
      (node (ref "B4") (pin "4") (pinfunction "A_4") (pintype "passive"))
      (node (ref "R38") (pin "2") (pinfunction "2_2") (pintype "passive"))
    )
    (net (code "64") (name "Net-(B4-B1)") (class "Default")
      (node (ref "B4") (pin "3") (pinfunction "B1_3") (pintype "passive"))
      (node (ref "R32") (pin "1") (pinfunction "1_1") (pintype "passive"))
    )
    (net (code "65") (name "Net-(B4-B2)") (class "Default")
      (node (ref "B4") (pin "1") (pinfunction "B2_1") (pintype "passive"))
      (node (ref "R36") (pin "1") (pinfunction "1_1") (pintype "passive"))
    )
    (net (code "66") (name "Net-(B4-S)") (class "Default")
      (node (ref "B4") (pin "6") (pinfunction "S_6") (pintype "passive"))
      (node (ref "R40") (pin "1") (pinfunction "1_1") (pintype "passive"))
    )
    (net (code "67") (name "Net-(B5-1Y)") (class "Default")
      (node (ref "B5") (pin "3") (pinfunction "1Y_3") (pintype "passive"))
      (node (ref "R41") (pin "2") (pinfunction "2_2") (pintype "passive"))
    )
    (net (code "68") (name "Net-(B5-2Y)") (class "Default")
      (node (ref "B5") (pin "5") (pinfunction "2Y_5") (pintype "passive"))
      (node (ref "R46") (pin "2") (pinfunction "2_2") (pintype "passive"))
    )
    (net (code "69") (name "Net-(B5-3Y)") (class "Default")
      (node (ref "B5") (pin "11") (pinfunction "3Y_11") (pintype "passive"))
      (node (ref "R51") (pin "2") (pinfunction "2_2") (pintype "passive"))
    )
    (net (code "70") (name "Net-(B5-4Y)") (class "Default")
      (node (ref "B5") (pin "13") (pinfunction "4Y_13") (pintype "passive"))
      (node (ref "R52") (pin "2") (pinfunction "2_2") (pintype "passive"))
    )
    (net (code "71") (name "Net-(B5-G)") (class "Default")
      (node (ref "B5") (pin "4") (pinfunction "G_4") (pintype "passive"))
      (node (ref "R53") (pin "1") (pinfunction "1_1") (pintype "passive"))
    )
    (net (code "72") (name "Net-(B5-~{G})") (class "Default")
      (node (ref "B5") (pin "12") (pinfunction "~{G}_12") (pintype "passive"))
      (node (ref "R54") (pin "1") (pinfunction "1_1") (pintype "passive"))
    )
    (net (code "73") (name "Net-(B6-A)") (class "Default")
      (node (ref "B6") (pin "4") (pinfunction "A_4") (pintype "passive"))
      (node (ref "R47") (pin "2") (pinfunction "2_2") (pintype "passive"))
    )
    (net (code "74") (name "Net-(B6-B1)") (class "Default")
      (node (ref "B6") (pin "3") (pinfunction "B1_3") (pintype "passive"))
      (node (ref "R42") (pin "1") (pinfunction "1_1") (pintype "passive"))
    )
    (net (code "75") (name "Net-(B6-B2)") (class "Default")
      (node (ref "B6") (pin "1") (pinfunction "B2_1") (pintype "passive"))
      (node (ref "R44") (pin "1") (pinfunction "1_1") (pintype "passive"))
    )
    (net (code "76") (name "Net-(B6-S)") (class "Default")
      (node (ref "B6") (pin "6") (pinfunction "S_6") (pintype "passive"))
      (node (ref "R49") (pin "1") (pinfunction "1_1") (pintype "passive"))
    )
    (net (code "77") (name "Net-(B7-A)") (class "Default")
      (node (ref "B7") (pin "4") (pinfunction "A_4") (pintype "passive"))
      (node (ref "R48") (pin "2") (pinfunction "2_2") (pintype "passive"))
    )
    (net (code "78") (name "Net-(B7-B1)") (class "Default")
      (node (ref "B7") (pin "3") (pinfunction "B1_3") (pintype "passive"))
      (node (ref "R43") (pin "1") (pinfunction "1_1") (pintype "passive"))
    )
    (net (code "79") (name "Net-(B7-B2)") (class "Default")
      (node (ref "B7") (pin "1") (pinfunction "B2_1") (pintype "passive"))
      (node (ref "R45") (pin "1") (pinfunction "1_1") (pintype "passive"))
    )
    (net (code "80") (name "Net-(B7-S)") (class "Default")
      (node (ref "B7") (pin "6") (pinfunction "S_6") (pintype "passive"))
      (node (ref "R50") (pin "1") (pinfunction "1_1") (pintype "passive"))
    )
    (net (code "81") (name "Net-(B8-A)") (class "Default")
      (node (ref "B8") (pin "4") (pinfunction "A_4") (pintype "passive"))
      (node (ref "R59") (pin "2") (pinfunction "2_2") (pintype "passive"))
    )
    (net (code "82") (name "Net-(B8-B1)") (class "Default")
      (node (ref "B8") (pin "3") (pinfunction "B1_3") (pintype "passive"))
      (node (ref "R55") (pin "1") (pinfunction "1_1") (pintype "passive"))
    )
    (net (code "83") (name "Net-(B8-B2)") (class "Default")
      (node (ref "B8") (pin "1") (pinfunction "B2_1") (pintype "passive"))
      (node (ref "R57") (pin "1") (pinfunction "1_1") (pintype "passive"))
    )
    (net (code "84") (name "Net-(B8-S)") (class "Default")
      (node (ref "B8") (pin "6") (pinfunction "S_6") (pintype "passive"))
      (node (ref "R61") (pin "1") (pinfunction "1_1") (pintype "passive"))
    )
    (net (code "85") (name "Net-(B9-A)") (class "Default")
      (node (ref "B9") (pin "4") (pinfunction "A_4") (pintype "passive"))
      (node (ref "R60") (pin "2") (pinfunction "2_2") (pintype "passive"))
    )
    (net (code "86") (name "Net-(B9-B1)") (class "Default")
      (node (ref "B9") (pin "3") (pinfunction "B1_3") (pintype "passive"))
      (node (ref "R56") (pin "1") (pinfunction "1_1") (pintype "passive"))
    )
    (net (code "87") (name "Net-(B9-B2)") (class "Default")
      (node (ref "B9") (pin "1") (pinfunction "B2_1") (pintype "passive"))
      (node (ref "R58") (pin "1") (pinfunction "1_1") (pintype "passive"))
    )
    (net (code "88") (name "Net-(B9-S)") (class "Default")
      (node (ref "B9") (pin "6") (pinfunction "S_6") (pintype "passive"))
      (node (ref "R62") (pin "1") (pinfunction "1_1") (pintype "passive"))
    )
    (net (code "89") (name "Net-(B10-1Y)") (class "Default")
      (node (ref "B10") (pin "3") (pinfunction "1Y_3") (pintype "passive"))
      (node (ref "R63") (pin "2") (pinfunction "2_2") (pintype "passive"))
    )
    (net (code "90") (name "Net-(B10-2Y)") (class "Default")
      (node (ref "B10") (pin "5") (pinfunction "2Y_5") (pintype "passive"))
      (node (ref "R64") (pin "2") (pinfunction "2_2") (pintype "passive"))
    )
    (net (code "91") (name "Net-(B10-3Y)") (class "Default")
      (node (ref "B10") (pin "11") (pinfunction "3Y_11") (pintype "passive"))
      (node (ref "R65") (pin "2") (pinfunction "2_2") (pintype "passive"))
    )
    (net (code "92") (name "Net-(B10-4Y)") (class "Default")
      (node (ref "B10") (pin "13") (pinfunction "4Y_13") (pintype "passive"))
      (node (ref "R66") (pin "2") (pinfunction "2_2") (pintype "passive"))
    )
    (net (code "93") (name "Net-(B10-G)") (class "Default")
      (node (ref "B10") (pin "4") (pinfunction "G_4") (pintype "passive"))
      (node (ref "R67") (pin "1") (pinfunction "1_1") (pintype "passive"))
    )
    (net (code "94") (name "Net-(B10-~{G})") (class "Default")
      (node (ref "B10") (pin "12") (pinfunction "~{G}_12") (pintype "passive"))
      (node (ref "R68") (pin "1") (pinfunction "1_1") (pintype "passive"))
    )
    (net (code "95") (name "Net-(H1-Pad1)") (class "Default")
      (node (ref "H1") (pin "1") (pinfunction "1_1") (pintype "passive"))
      (node (ref "R1") (pin "2") (pinfunction "2_2") (pintype "passive"))
    )
    (net (code "96") (name "Net-(H1-Pad3)") (class "Default")
      (node (ref "H1") (pin "3") (pinfunction "3_3") (pintype "passive"))
      (node (ref "R2") (pin "2") (pinfunction "2_2") (pintype "passive"))
    )
    (net (code "97") (name "Net-(H1-Pad5)") (class "Default")
      (node (ref "H1") (pin "5") (pinfunction "5_5") (pintype "passive"))
      (node (ref "R3") (pin "2") (pinfunction "2_2") (pintype "passive"))
    )
    (net (code "98") (name "Net-(H1-Pad7)") (class "Default")
      (node (ref "H1") (pin "7") (pinfunction "7_7") (pintype "passive"))
      (node (ref "R4") (pin "2") (pinfunction "2_2") (pintype "passive"))
    )
    (net (code "99") (name "Net-(H1-Pad9)") (class "Default")
      (node (ref "H1") (pin "9") (pinfunction "9_9") (pintype "passive"))
      (node (ref "R5") (pin "2") (pinfunction "2_2") (pintype "passive"))
    )
    (net (code "100") (name "Net-(H1-Pad11)") (class "Default")
      (node (ref "H1") (pin "11") (pinfunction "11_11") (pintype "passive"))
      (node (ref "R6") (pin "2") (pinfunction "2_2") (pintype "passive"))
    )
    (net (code "101") (name "Net-(H1-Pad13)") (class "Default")
      (node (ref "H1") (pin "13") (pinfunction "13_13") (pintype "passive"))
      (node (ref "R7") (pin "2") (pinfunction "2_2") (pintype "passive"))
    )
    (net (code "102") (name "Net-(H1-Pad15)") (class "Default")
      (node (ref "H1") (pin "15") (pinfunction "15_15") (pintype "passive"))
      (node (ref "R8") (pin "2") (pinfunction "2_2") (pintype "passive"))
    )
    (net (code "103") (name "Net-(H2-Pad1)") (class "Default")
      (node (ref "H2") (pin "1") (pinfunction "1_1") (pintype "passive"))
      (node (ref "R17") (pin "2") (pinfunction "2_2") (pintype "passive"))
    )
    (net (code "104") (name "Net-(H2-Pad2)") (class "Default")
      (node (ref "H2") (pin "2") (pinfunction "2_2") (pintype "passive"))
      (node (ref "R18") (pin "1") (pinfunction "1_1") (pintype "passive"))
    )
    (net (code "105") (name "Net-(H2-Pad3)") (class "Default")
      (node (ref "H2") (pin "3") (pinfunction "3_3") (pintype "passive"))
      (node (ref "R19") (pin "2") (pinfunction "2_2") (pintype "passive"))
    )
    (net (code "106") (name "Net-(H2-Pad4)") (class "Default")
      (node (ref "H2") (pin "4") (pinfunction "4_4") (pintype "passive"))
      (node (ref "R20") (pin "1") (pinfunction "1_1") (pintype "passive"))
    )
    (net (code "107") (name "Net-(H2-Pad5)") (class "Default")
      (node (ref "H2") (pin "5") (pinfunction "5_5") (pintype "passive"))
      (node (ref "R21") (pin "2") (pinfunction "2_2") (pintype "passive"))
    )
    (net (code "108") (name "Net-(H2-Pad6)") (class "Default")
      (node (ref "H2") (pin "6") (pinfunction "6_6") (pintype "passive"))
      (node (ref "R22") (pin "1") (pinfunction "1_1") (pintype "passive"))
    )
    (net (code "109") (name "Net-(H2-Pad7)") (class "Default")
      (node (ref "H2") (pin "7") (pinfunction "7_7") (pintype "passive"))
      (node (ref "R23") (pin "2") (pinfunction "2_2") (pintype "passive"))
    )
    (net (code "110") (name "Net-(H2-Pad8)") (class "Default")
      (node (ref "H2") (pin "8") (pinfunction "8_8") (pintype "passive"))
      (node (ref "R24") (pin "1") (pinfunction "1_1") (pintype "passive"))
    )
    (net (code "111") (name "Net-(H2-Pad9)") (class "Default")
      (node (ref "H2") (pin "9") (pinfunction "9_9") (pintype "passive"))
      (node (ref "R25") (pin "2") (pinfunction "2_2") (pintype "passive"))
    )
    (net (code "112") (name "Net-(H2-Pad10)") (class "Default")
      (node (ref "H2") (pin "10") (pinfunction "10_10") (pintype "passive"))
      (node (ref "R26") (pin "1") (pinfunction "1_1") (pintype "passive"))
    )
    (net (code "113") (name "Net-(H2-Pad11)") (class "Default")
      (node (ref "H2") (pin "11") (pinfunction "11_11") (pintype "passive"))
      (node (ref "R27") (pin "2") (pinfunction "2_2") (pintype "passive"))
    )
    (net (code "114") (name "Net-(H2-Pad12)") (class "Default")
      (node (ref "H2") (pin "12") (pinfunction "12_12") (pintype "passive"))
      (node (ref "R28") (pin "1") (pinfunction "1_1") (pintype "passive"))
    )
    (net (code "115") (name "Net-(H2-Pad13)") (class "Default")
      (node (ref "H2") (pin "13") (pinfunction "13_13") (pintype "passive"))
      (node (ref "R29") (pin "2") (pinfunction "2_2") (pintype "passive"))
    )
    (net (code "116") (name "Net-(H2-Pad14)") (class "Default")
      (node (ref "H2") (pin "14") (pinfunction "14_14") (pintype "passive"))
      (node (ref "R30") (pin "1") (pinfunction "1_1") (pintype "passive"))
    )
    (net (code "117") (name "Net-(H2-Pad15)") (class "Default")
      (node (ref "H2") (pin "15") (pinfunction "15_15") (pintype "passive"))
      (node (ref "R33") (pin "2") (pinfunction "2_2") (pintype "passive"))
    )
    (net (code "118") (name "Net-(H2-Pad16)") (class "Default")
      (node (ref "H2") (pin "16") (pinfunction "16_16") (pintype "passive"))
      (node (ref "R34") (pin "1") (pinfunction "1_1") (pintype "passive"))
    )
  )
)
